# DKBLE11x-OTA-AddOn-0_1.net
KiCad netlist of a schematic drawn in EAGLE
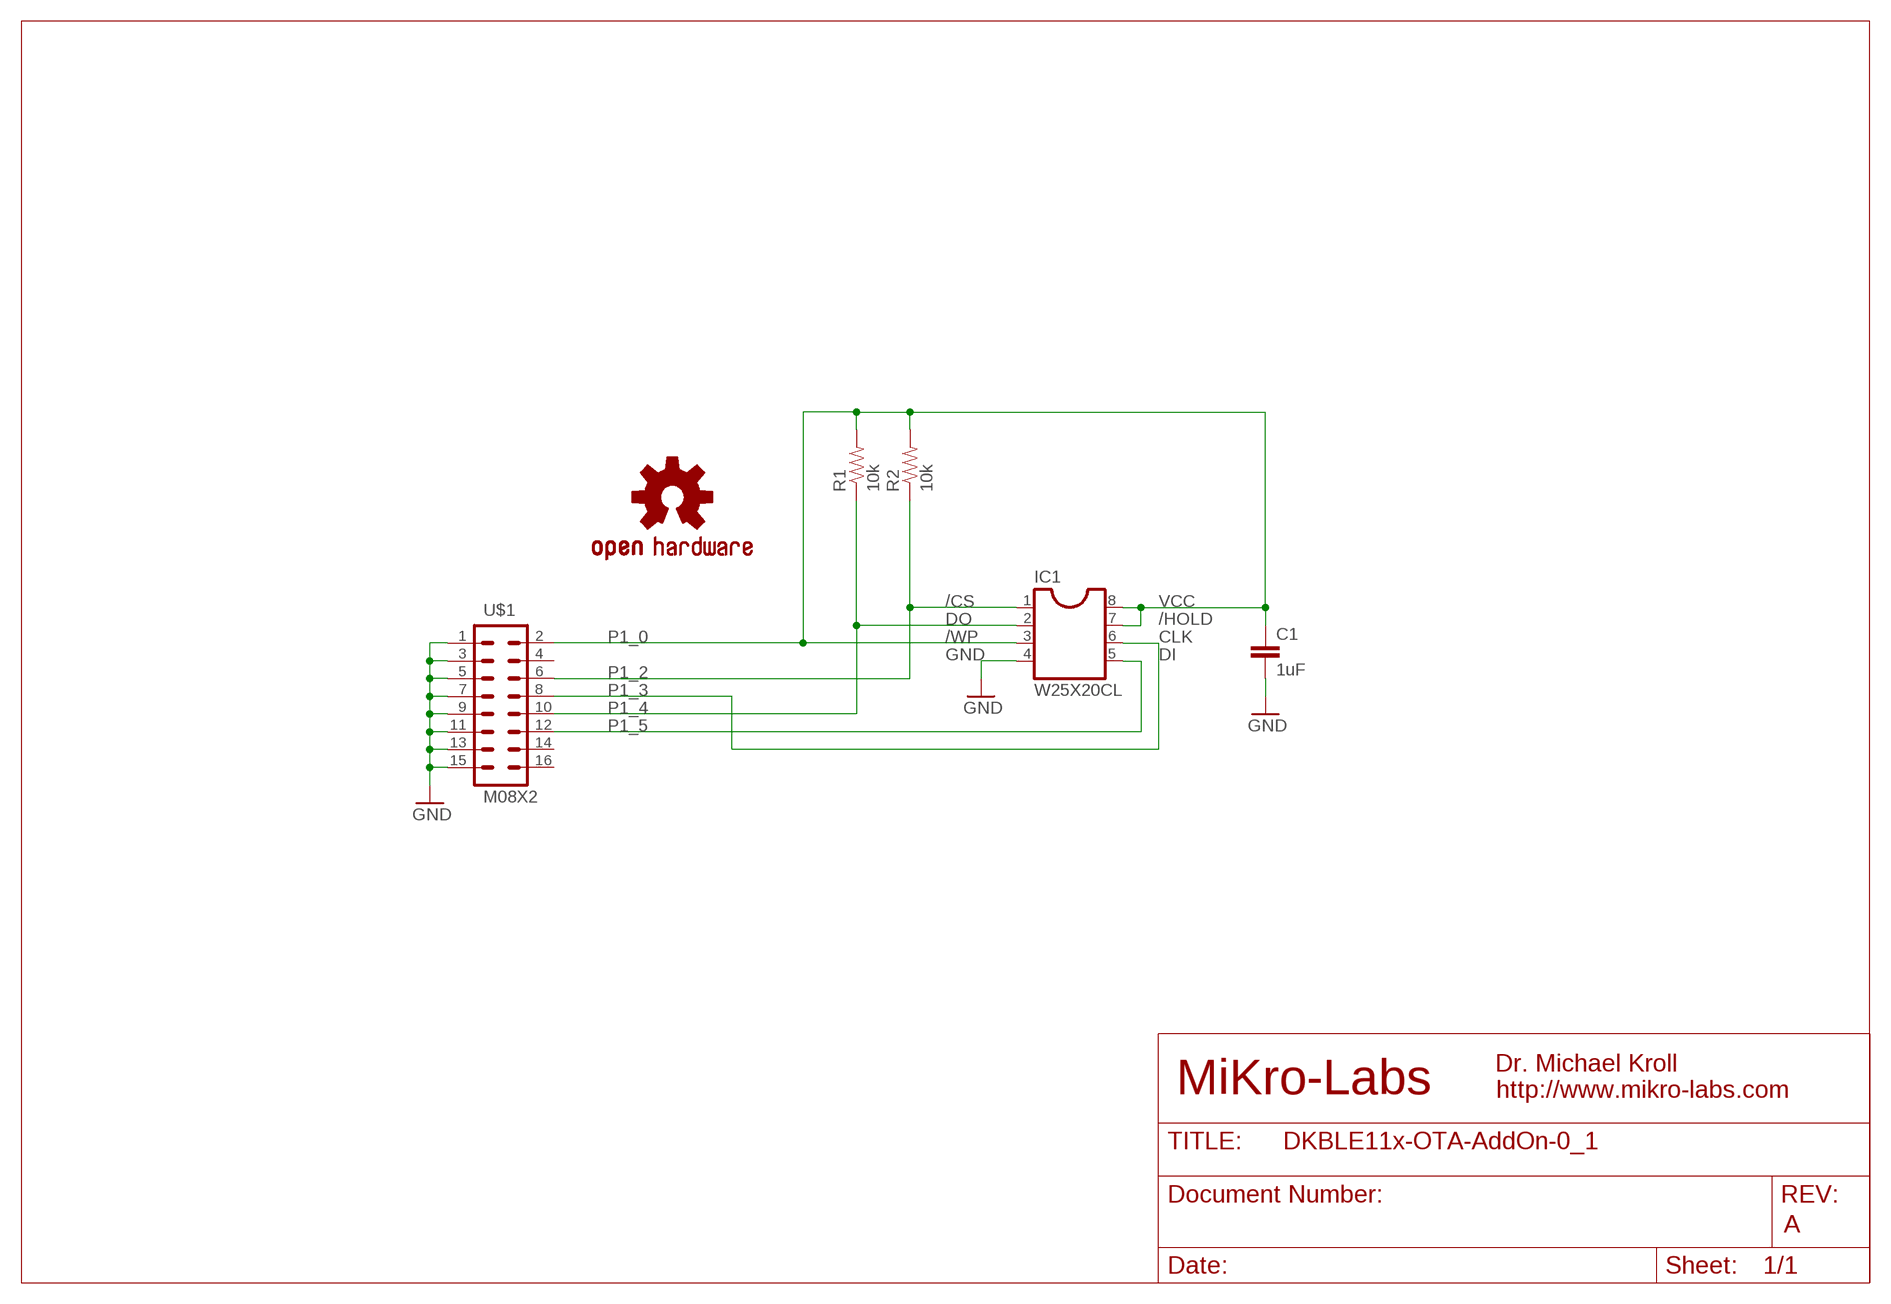
[diagram p0: schematic, sheet 1]

(export (version "E")
  (design (tool "Eeschema 10.0.6"))
  (components
    (comp (ref "C1")
      (value "1uF")
      (footprint "eagle-import:0603-CAP")
      (libsource (lib "eagle-import") (part "CAP0603-CAP"))
    )
    (comp (ref "IC1")
      (value "W25X20CL")
      (footprint "eagle-import:SO-8")
      (libsource (lib "eagle-import") (part "IC_DIL8-SOIC8"))
    )
    (comp (ref "LOGO1")
      (value "OSHW-LOGOS")
      (footprint "eagle-import:OSHW-LOGO-S")
      (libsource (lib "eagle-import") (part "OSHW-LOGOS"))
    )
    (comp (ref "R1")
      (value "10k")
      (footprint "eagle-import:0603-RES")
      (libsource (lib "eagle-import") (part "RESISTOR0603-RES"))
    )
    (comp (ref "R2")
      (value "10k")
      (footprint "eagle-import:0603-RES")
      (libsource (lib "eagle-import") (part "RESISTOR0603-RES"))
    )
    (comp (ref "U$1")
      (value "M08X2")
      (footprint "eagle-import:2X8")
      (libsource (lib "eagle-import") (part "M08X2"))
    )
  )
  (nets
    (net (code "1") (name "GND") (class "Default")
      (node (ref "C1") (pin "2") (pinfunction "2_2") (pintype "passive"))
      (node (ref "IC1") (pin "4") (pinfunction "4_4") (pintype "bidirectional"))
      (node (ref "U$1") (pin "1") (pinfunction "1_1") (pintype "passive"))
      (node (ref "U$1") (pin "11") (pinfunction "11_11") (pintype "passive"))
      (node (ref "U$1") (pin "13") (pinfunction "13_13") (pintype "passive"))
      (node (ref "U$1") (pin "15") (pinfunction "15_15") (pintype "passive"))
      (node (ref "U$1") (pin "3") (pinfunction "3_3") (pintype "passive"))
      (node (ref "U$1") (pin "5") (pinfunction "5_5") (pintype "passive"))
      (node (ref "U$1") (pin "7") (pinfunction "7_7") (pintype "passive"))
      (node (ref "U$1") (pin "9") (pinfunction "9_9") (pintype "passive"))
    )
    (net (code "2") (name "Net-(C1-Pad1)") (class "Default")
      (node (ref "C1") (pin "1") (pinfunction "1_1") (pintype "passive"))
      (node (ref "IC1") (pin "3") (pinfunction "3_3") (pintype "bidirectional"))
      (node (ref "IC1") (pin "7") (pinfunction "7_7") (pintype "bidirectional"))
      (node (ref "IC1") (pin "8") (pinfunction "8_8") (pintype "bidirectional"))
      (node (ref "R1") (pin "2") (pinfunction "2_2") (pintype "passive"))
      (node (ref "R2") (pin "2") (pinfunction "2_2") (pintype "passive"))
      (node (ref "U$1") (pin "2") (pinfunction "2_2") (pintype "passive"))
    )
    (net (code "3") (name "Net-(IC1-Pad1)") (class "Default")
      (node (ref "IC1") (pin "1") (pinfunction "1_1") (pintype "bidirectional"))
      (node (ref "R2") (pin "1") (pinfunction "1_1") (pintype "passive"))
      (node (ref "U$1") (pin "6") (pinfunction "6_6") (pintype "passive"))
    )
    (net (code "4") (name "Net-(IC1-Pad2)") (class "Default")
      (node (ref "IC1") (pin "2") (pinfunction "2_2") (pintype "bidirectional"))
      (node (ref "R1") (pin "1") (pinfunction "1_1") (pintype "passive"))
      (node (ref "U$1") (pin "10") (pinfunction "10_10") (pintype "passive"))
    )
    (net (code "5") (name "Net-(IC1-Pad5)") (class "Default")
      (node (ref "IC1") (pin "5") (pinfunction "5_5") (pintype "bidirectional"))
      (node (ref "U$1") (pin "12") (pinfunction "12_12") (pintype "passive"))
    )
    (net (code "6") (name "Net-(IC1-Pad6)") (class "Default")
      (node (ref "IC1") (pin "6") (pinfunction "6_6") (pintype "bidirectional"))
      (node (ref "U$1") (pin "8") (pinfunction "8_8") (pintype "passive"))
    )
    (net (code "7") (name "unconnected-(U$1-Pad4)") (class "Default")
      (node (ref "U$1") (pin "4") (pinfunction "4_4") (pintype "passive"))
    )
    (net (code "8") (name "unconnected-(U$1-Pad14)") (class "Default")
      (node (ref "U$1") (pin "14") (pinfunction "14_14") (pintype "passive"))
    )
    (net (code "9") (name "unconnected-(U$1-Pad16)") (class "Default")
      (node (ref "U$1") (pin "16") (pinfunction "16_16") (pintype "passive"))
    )
  )
)
